# LAMEBOY.net
KiCad netlist of a schematic drawn in EAGLE
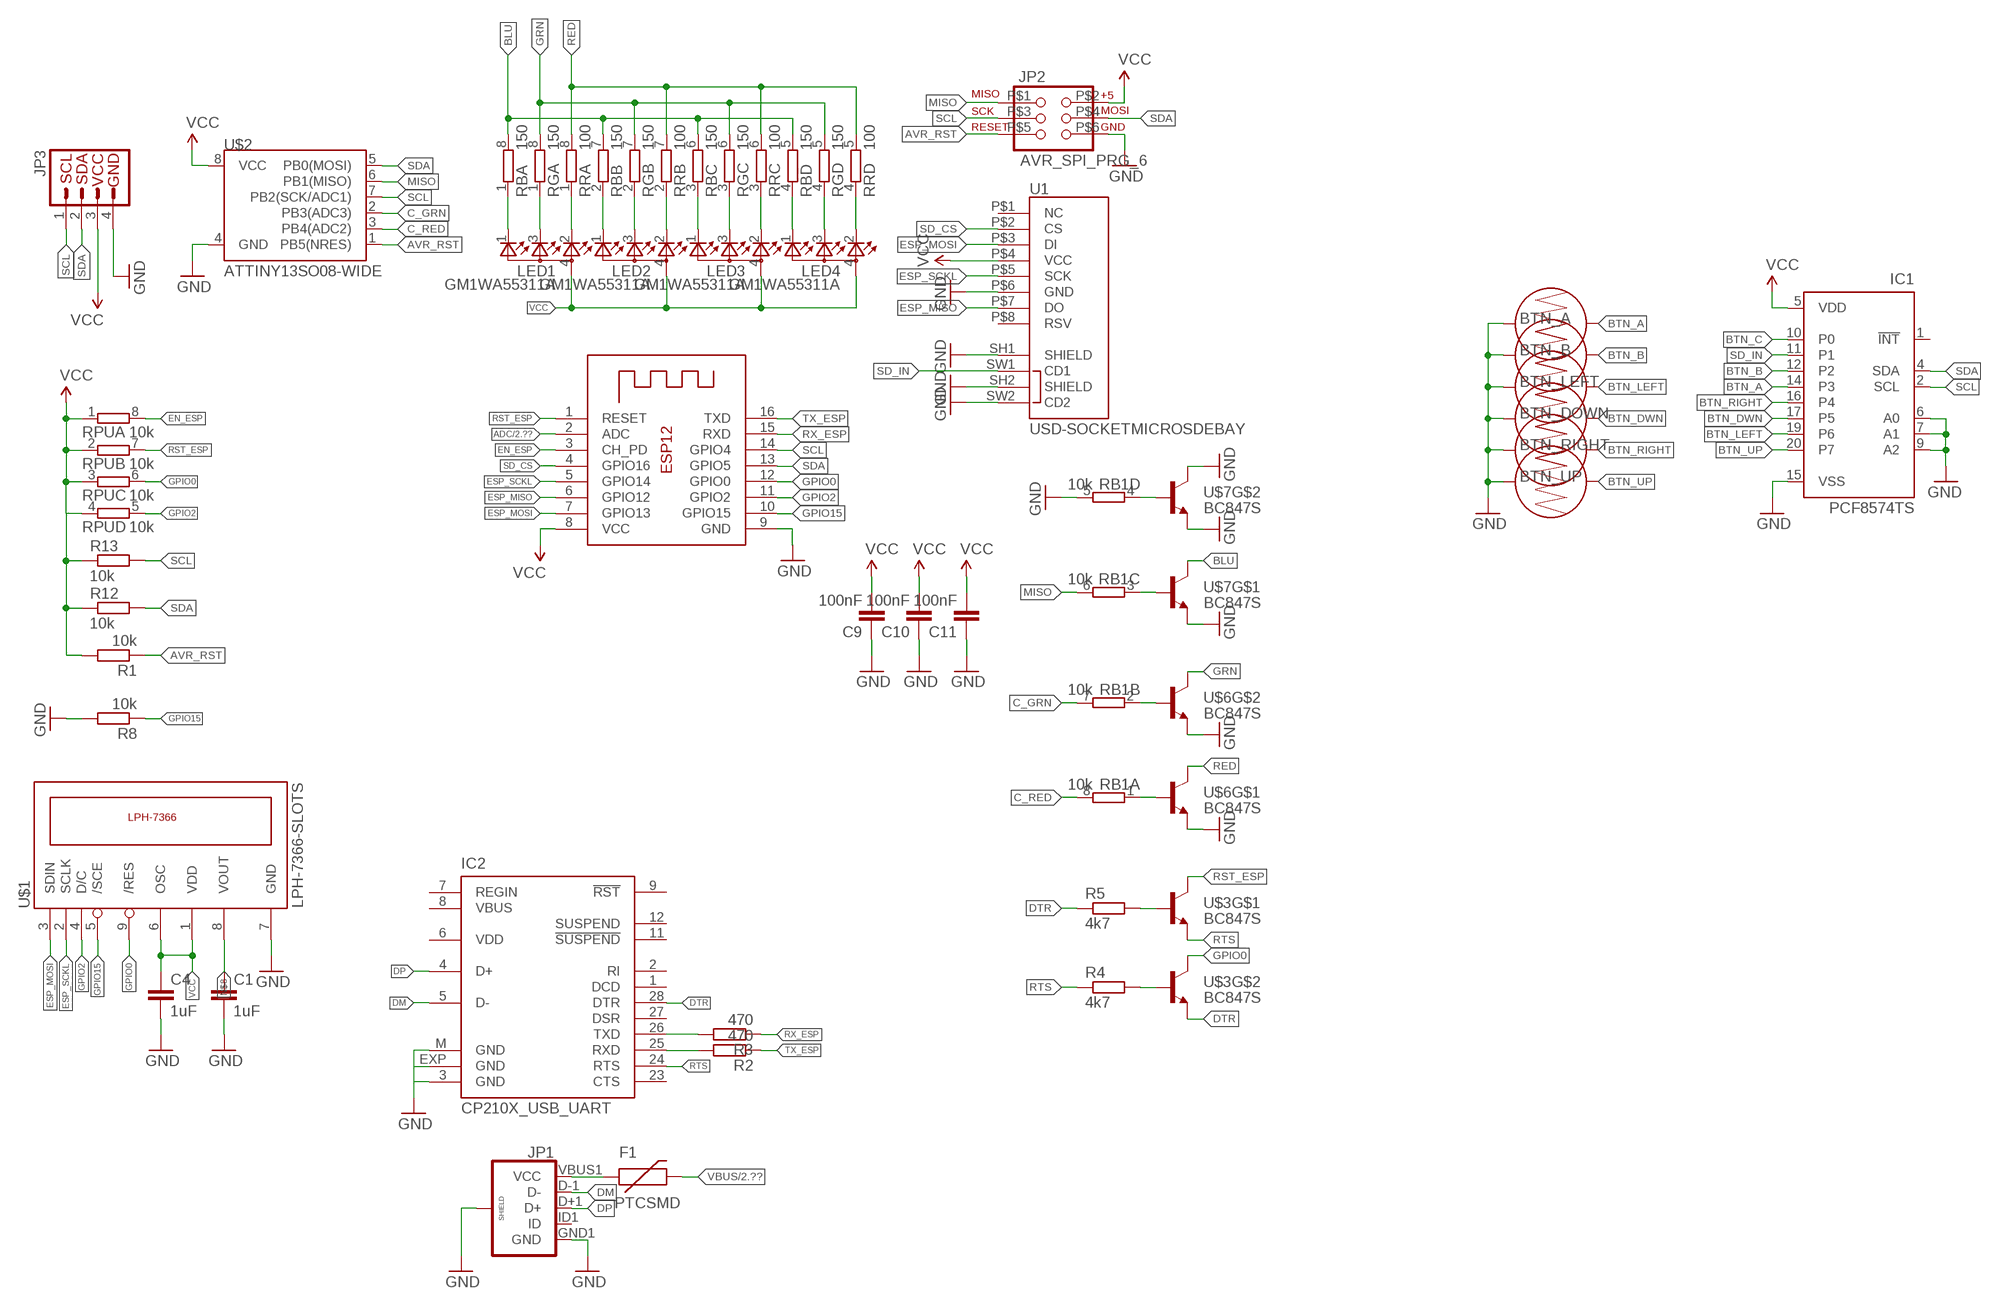
[diagram p0: schematic, sheet 1]
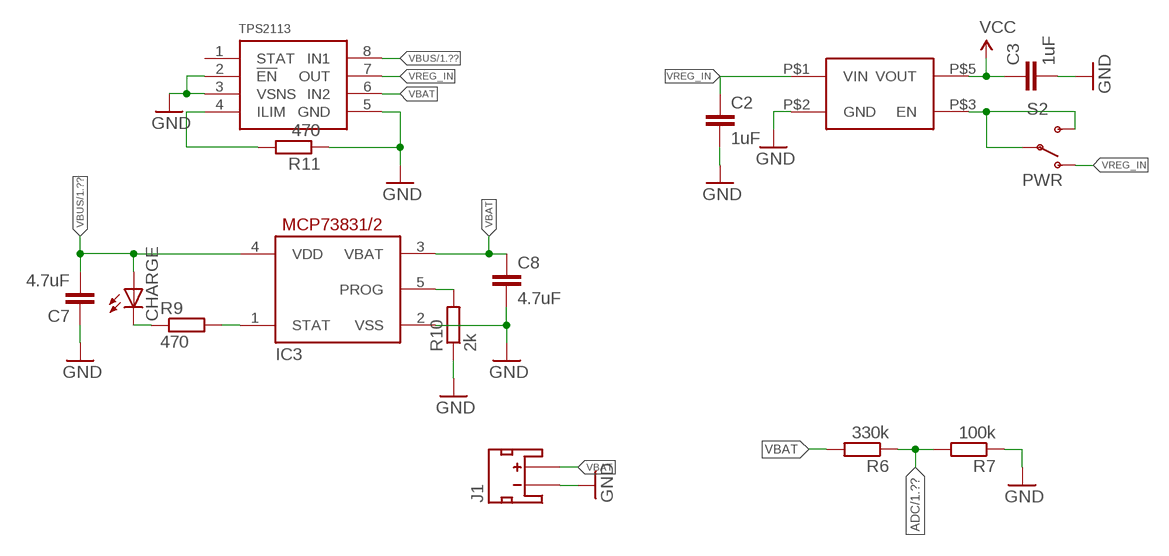
[diagram p1: schematic, sheet 2]

(export (version "E")
  (design (tool "Eeschema 10.0.6"))
  (components
    (comp (ref "C2")
      (value "1uF")
      (footprint "eagle-import:C0805")
      (libsource (lib "eagle-import") (part "C-EUC0805"))
    )
    (comp (ref "C3")
      (value "1uF")
      (footprint "eagle-import:C0805")
      (libsource (lib "eagle-import") (part "C-EUC0805"))
    )
    (comp (ref "C7")
      (value "4.7uF")
      (footprint "eagle-import:C0805")
      (libsource (lib "eagle-import") (part "C-EUC0805"))
    )
    (comp (ref "C8")
      (value "4.7uF")
      (footprint "eagle-import:C0805")
      (libsource (lib "eagle-import") (part "C-EUC0805"))
    )
    (comp (ref "CHARGE")
      (value "LEDCHARLIE")
      (footprint "eagle-import:CHIPLED_0603_CHARLIE")
      (libsource (lib "eagle-import") (part "LEDCHARLIE"))
    )
    (comp (ref "IC3")
      (value "MCP73831")
      (footprint "eagle-import:SOT23-5L")
      (libsource (lib "eagle-import") (part "MCP73831/OT"))
    )
    (comp (ref "J1")
      (value "JST_2MM_MALE")
      (footprint "eagle-import:JST-2-SMD")
      (libsource (lib "eagle-import") (part "JST_2MM_MALE"))
    )
    (comp (ref "R6")
      (value "330k")
      (footprint "eagle-import:R0805")
      (libsource (lib "eagle-import") (part "R-EU_R0805"))
    )
    (comp (ref "R7")
      (value "100k")
      (footprint "eagle-import:R0805")
      (libsource (lib "eagle-import") (part "R-EU_R0805"))
    )
    (comp (ref "R9")
      (value "470")
      (footprint "eagle-import:R0805")
      (libsource (lib "eagle-import") (part "R-EU_R0805"))
    )
    (comp (ref "R10")
      (value "2k")
      (footprint "eagle-import:R0805")
      (libsource (lib "eagle-import") (part "R-EU_R0805"))
    )
    (comp (ref "R11")
      (value "470")
      (footprint "eagle-import:M0805")
      (libsource (lib "eagle-import") (part "resistor_R-EU_M0805"))
    )
    (comp (ref "S2")
      (value "PWR")
      (footprint "eagle-import:SWITCH-SPST-SMD-A")
      (libsource (lib "eagle-import") (part "SWITCH-SPDT-SMD-A"))
    )
    (comp (ref "U$4")
      (value "TPS2113-PW")
      (footprint "eagle-import:TEXAS-PW")
      (libsource (lib "eagle-import") (part "TPS2113-PW"))
    )
    (comp (ref "U$9")
      (value "AP2112KAP2112K")
      (footprint "eagle-import:AP2112")
      (libsource (lib "eagle-import") (part "AP2112KAP2112K"))
    )
    (comp (ref "BTN_A")
      (value "BUTTON-CONDUCTIVESMD")
      (footprint "eagle-import:BUTTON-CONDUCTIVE")
      (libsource (lib "eagle-import") (part "BUTTON-CONDUCTIVESMD"))
    )
    (comp (ref "BTN_B")
      (value "BUTTON-CONDUCTIVESMD")
      (footprint "eagle-import:BUTTON-CONDUCTIVE")
      (libsource (lib "eagle-import") (part "BUTTON-CONDUCTIVESMD"))
    )
    (comp (ref "BTN_DOWN")
      (value "BUTTON-CONDUCTIVESMD")
      (footprint "eagle-import:BUTTON-CONDUCTIVE")
      (libsource (lib "eagle-import") (part "BUTTON-CONDUCTIVESMD"))
    )
    (comp (ref "BTN_LEFT")
      (value "BUTTON-CONDUCTIVESMD")
      (footprint "eagle-import:BUTTON-CONDUCTIVE")
      (libsource (lib "eagle-import") (part "BUTTON-CONDUCTIVESMD"))
    )
    (comp (ref "BTN_RIGHT")
      (value "BUTTON-CONDUCTIVESMD")
      (footprint "eagle-import:BUTTON-CONDUCTIVE")
      (libsource (lib "eagle-import") (part "BUTTON-CONDUCTIVESMD"))
    )
    (comp (ref "BTN_UP")
      (value "BUTTON-CONDUCTIVESMD")
      (footprint "eagle-import:BUTTON-CONDUCTIVE")
      (libsource (lib "eagle-import") (part "BUTTON-CONDUCTIVESMD"))
    )
    (comp (ref "C1")
      (value "1uF")
      (footprint "eagle-import:C0805")
      (libsource (lib "eagle-import") (part "C-EUC0805"))
    )
    (comp (ref "C4")
      (value "1uF")
      (footprint "eagle-import:C0805")
      (libsource (lib "eagle-import") (part "C-EUC0805"))
    )
    (comp (ref "C9")
      (value "100nF")
      (footprint "eagle-import:C0805")
      (libsource (lib "eagle-import") (part "C-EUC0805"))
    )
    (comp (ref "C10")
      (value "100nF")
      (footprint "eagle-import:C0805")
      (libsource (lib "eagle-import") (part "C-EUC0805"))
    )
    (comp (ref "C11")
      (value "100nF")
      (footprint "eagle-import:C0805")
      (libsource (lib "eagle-import") (part "C-EUC0805"))
    )
    (comp (ref "F1")
      (value "PTCSMD")
      (footprint "eagle-import:PTC-1206")
      (libsource (lib "eagle-import") (part "PTCSMD"))
    )
    (comp (ref "IC1")
      (value "PCF8574TS")
      (footprint "eagle-import:SSOP20")
      (fields (field (name "MPN") "PCF8574TS/3,118"))
      (libsource (lib "eagle-import") (part "PCF8574TS"))
    )
    (comp (ref "IC2")
      (value "CP210X_USB_UART")
      (footprint "eagle-import:MLP28")
      (libsource (lib "eagle-import") (part "CP210X_USB_UART"))
    )
    (comp (ref "JP1")
      (value "USB_MICROB_PLUG-IDK")
      (footprint "eagle-import:USB-AB-MICRO-SMD_SLOT")
      (libsource (lib "eagle-import") (part "USB_MICROB_PLUG-IDK"))
    )
    (comp (ref "JP2")
      (value "AVR_SPI_PRG_6")
      (footprint "eagle-import:2X3_SMD_PAD")
      (libsource (lib "eagle-import") (part "AVR_SPI_PRG_6"))
    )
    (comp (ref "JP3")
      (value "I2C_STANDARDI2C_JST")
      (footprint "eagle-import:S4B-PH")
      (libsource (lib "eagle-import") (part "I2C_STANDARDI2C_JST"))
    )
    (comp (ref "LED1")
      (value "GM1WA55311A")
      (footprint "eagle-import:GM1WA55311A")
      (libsource (lib "eagle-import") (part "GM1WA55311A"))
    )
    (comp (ref "LED2")
      (value "GM1WA55311A")
      (footprint "eagle-import:GM1WA55311A")
      (libsource (lib "eagle-import") (part "GM1WA55311A"))
    )
    (comp (ref "LED3")
      (value "GM1WA55311A")
      (footprint "eagle-import:GM1WA55311A")
      (libsource (lib "eagle-import") (part "GM1WA55311A"))
    )
    (comp (ref "LED4")
      (value "GM1WA55311A")
      (footprint "eagle-import:GM1WA55311A")
      (libsource (lib "eagle-import") (part "GM1WA55311A"))
    )
    (comp (ref "R1")
      (value "10k")
      (footprint "eagle-import:R0805")
      (libsource (lib "eagle-import") (part "R-EU_R0805"))
    )
    (comp (ref "R2")
      (value "470")
      (footprint "eagle-import:R0805")
      (libsource (lib "eagle-import") (part "R-EU_R0805"))
    )
    (comp (ref "R3")
      (value "470")
      (footprint "eagle-import:R0805")
      (libsource (lib "eagle-import") (part "R-EU_R0805"))
    )
    (comp (ref "R4")
      (value "4k7")
      (footprint "eagle-import:R0805")
      (libsource (lib "eagle-import") (part "R-EU_R0805"))
    )
    (comp (ref "R5")
      (value "4k7")
      (footprint "eagle-import:R0805")
      (libsource (lib "eagle-import") (part "R-EU_R0805"))
    )
    (comp (ref "R8")
      (value "10k")
      (footprint "eagle-import:R0805")
      (libsource (lib "eagle-import") (part "R-EU_R0805"))
    )
    (comp (ref "R12")
      (value "10k")
      (footprint "eagle-import:R0805")
      (libsource (lib "eagle-import") (part "R-EU_R0805"))
    )
    (comp (ref "R13")
      (value "10k")
      (footprint "eagle-import:R0805")
      (libsource (lib "eagle-import") (part "R-EU_R0805"))
    )
    (comp (ref "RB")
      (value "150")
      (footprint "eagle-import:0603-ARC")
      (libsource (lib "eagle-import") (part "4R-N0603-ARC"))
    )
    (comp (ref "RB1")
      (value "10k")
      (footprint "eagle-import:0603-ARC")
      (libsource (lib "eagle-import") (part "4R-N0603-ARC"))
    )
    (comp (ref "RG")
      (value "150")
      (footprint "eagle-import:0603-ARC")
      (libsource (lib "eagle-import") (part "4R-N0603-ARC"))
    )
    (comp (ref "RPU")
      (value "10k")
      (footprint "eagle-import:0603-ARC")
      (libsource (lib "eagle-import") (part "4R-N0603-ARC"))
    )
    (comp (ref "RR")
      (value "100")
      (footprint "eagle-import:0603-ARC")
      (libsource (lib "eagle-import") (part "4R-N0603-ARC"))
    )
    (comp (ref "U$1")
      (value "LPH-7366-SLOTS")
      (footprint "eagle-import:LPH-7366-SLOTS")
      (libsource (lib "eagle-import") (part "LPH-7366-SLOTS"))
    )
    (comp (ref "U$2")
      (value "ATTINY13SO08-WIDE")
      (footprint "eagle-import:SO08-EIAJ")
      (libsource (lib "eagle-import") (part "ATTINY13SO08-WIDE"))
    )
    (comp (ref "U$3")
      (value "BC847S")
      (footprint "eagle-import:SOT363")
      (libsource (lib "eagle-import") (part "MMDT3904"))
    )
    (comp (ref "U$6")
      (value "BC847S")
      (footprint "eagle-import:SOT363")
      (libsource (lib "eagle-import") (part "MMDT3904"))
    )
    (comp (ref "U$7")
      (value "BC847S")
      (footprint "eagle-import:SOT363")
      (libsource (lib "eagle-import") (part "MMDT3904"))
    )
    (comp (ref "U1")
      (value "USD-SOCKETMICROSDEBAY")
      (footprint "eagle-import:MICRO-SD-SOCKET-EBAY")
      (libsource (lib "eagle-import") (part "USD-SOCKETMICROSDEBAY"))
    )
    (comp (ref "X1")
      (value "ESP-12")
      (footprint "eagle-import:ESP-12")
      (libsource (lib "eagle-import") (part "ESP-12"))
    )
  )
  (nets
    (net (code "1") (name "ADC") (class "Default")
      (node (ref "R6") (pin "1") (pinfunction "1_1") (pintype "passive"))
      (node (ref "R7") (pin "2") (pinfunction "2_2") (pintype "passive"))
      (node (ref "X1") (pin "2") (pinfunction "ADC_2") (pintype "passive"))
    )
    (net (code "2") (name "AVR_RST") (class "Default")
      (node (ref "JP2") (pin "P$5") (pinfunction "5_P$5") (pintype "passive"))
      (node (ref "R1") (pin "1") (pinfunction "1_1") (pintype "passive"))
      (node (ref "U$2") (pin "1") (pinfunction "PB5(NRES)_1") (pintype "bidirectional"))
    )
    (net (code "3") (name "BLU") (class "Default")
      (node (ref "RB") (pin "5") (pinfunction "2_5") (pintype "passive"))
      (node (ref "RB") (pin "6") (pinfunction "2_6") (pintype "passive"))
      (node (ref "RB") (pin "7") (pinfunction "2_7") (pintype "passive"))
      (node (ref "RB") (pin "8") (pinfunction "2_8") (pintype "passive"))
      (node (ref "U$7") (pin "3") (pinfunction "C_3") (pintype "passive"))
    )
    (net (code "4") (name "BTN_A") (class "Default")
      (node (ref "BTN_A") (pin "2") (pinfunction "2_2") (pintype "passive"))
      (node (ref "IC1") (pin "14") (pinfunction "P3_14") (pintype "bidirectional"))
    )
    (net (code "5") (name "BTN_B") (class "Default")
      (node (ref "BTN_B") (pin "2") (pinfunction "2_2") (pintype "passive"))
      (node (ref "IC1") (pin "12") (pinfunction "P2_12") (pintype "bidirectional"))
    )
    (net (code "6") (name "BTN_C") (class "Default")
      (node (ref "IC1") (pin "10") (pinfunction "P0_10") (pintype "bidirectional"))
    )
    (net (code "7") (name "BTN_DWN") (class "Default")
      (node (ref "BTN_DOWN") (pin "2") (pinfunction "2_2") (pintype "passive"))
      (node (ref "IC1") (pin "17") (pinfunction "P5_17") (pintype "bidirectional"))
    )
    (net (code "8") (name "BTN_LEFT") (class "Default")
      (node (ref "BTN_LEFT") (pin "2") (pinfunction "2_2") (pintype "passive"))
      (node (ref "IC1") (pin "19") (pinfunction "P6_19") (pintype "bidirectional"))
    )
    (net (code "9") (name "BTN_RIGHT") (class "Default")
      (node (ref "BTN_RIGHT") (pin "2") (pinfunction "2_2") (pintype "passive"))
      (node (ref "IC1") (pin "16") (pinfunction "P4_16") (pintype "bidirectional"))
    )
    (net (code "10") (name "BTN_UP") (class "Default")
      (node (ref "BTN_UP") (pin "2") (pinfunction "2_2") (pintype "passive"))
      (node (ref "IC1") (pin "20") (pinfunction "P7_20") (pintype "bidirectional"))
    )
    (net (code "11") (name "C_GRN") (class "Default")
      (node (ref "RB1") (pin "7") (pinfunction "2_7") (pintype "passive"))
      (node (ref "U$2") (pin "2") (pinfunction "PB3(ADC3)_2") (pintype "bidirectional"))
    )
    (net (code "12") (name "C_RED") (class "Default")
      (node (ref "RB1") (pin "8") (pinfunction "2_8") (pintype "passive"))
      (node (ref "U$2") (pin "3") (pinfunction "PB4(ADC2)_3") (pintype "bidirectional"))
    )
    (net (code "13") (name "DM") (class "Default")
      (node (ref "IC2") (pin "5") (pinfunction "D-_5") (pintype "bidirectional"))
      (node (ref "JP1") (pin "D-1") (pinfunction "D-_D-1") (pintype "bidirectional"))
    )
    (net (code "14") (name "DP") (class "Default")
      (node (ref "IC2") (pin "4") (pinfunction "D+_4") (pintype "bidirectional"))
      (node (ref "JP1") (pin "D+1") (pinfunction "D+_D+1") (pintype "bidirectional"))
    )
    (net (code "15") (name "DTR") (class "Default")
      (node (ref "IC2") (pin "28") (pinfunction "DTR_28") (pintype "output"))
      (node (ref "R5") (pin "1") (pinfunction "1_1") (pintype "passive"))
      (node (ref "U$3") (pin "1") (pinfunction "E_1") (pintype "passive"))
    )
    (net (code "16") (name "EN_ESP") (class "Default")
      (node (ref "RPU") (pin "8") (pinfunction "2_8") (pintype "passive"))
      (node (ref "X1") (pin "3") (pinfunction "CH_PD_3") (pintype "input"))
    )
    (net (code "17") (name "ESP_MISO") (class "Default")
      (node (ref "U1") (pin "P$7") (pinfunction "DO_P$7") (pintype "bidirectional"))
      (node (ref "X1") (pin "6") (pinfunction "GPIO12_6") (pintype "bidirectional"))
    )
    (net (code "18") (name "ESP_MOSI") (class "Default")
      (node (ref "U$1") (pin "3") (pinfunction "SDIN_3") (pintype "input"))
      (node (ref "U1") (pin "P$3") (pinfunction "DI_P$3") (pintype "bidirectional"))
      (node (ref "X1") (pin "7") (pinfunction "GPIO13_7") (pintype "bidirectional"))
    )
    (net (code "19") (name "ESP_SCKL") (class "Default")
      (node (ref "U$1") (pin "2") (pinfunction "SCLK_2") (pintype "input"))
      (node (ref "U1") (pin "P$5") (pinfunction "SCK_P$5") (pintype "bidirectional"))
      (node (ref "X1") (pin "5") (pinfunction "GPIO14_5") (pintype "bidirectional"))
    )
    (net (code "20") (name "GND") (class "Default")
      (node (ref "BTN_A") (pin "1") (pinfunction "1_1") (pintype "passive"))
      (node (ref "BTN_B") (pin "1") (pinfunction "1_1") (pintype "passive"))
      (node (ref "BTN_DOWN") (pin "1") (pinfunction "1_1") (pintype "passive"))
      (node (ref "BTN_LEFT") (pin "1") (pinfunction "1_1") (pintype "passive"))
      (node (ref "BTN_RIGHT") (pin "1") (pinfunction "1_1") (pintype "passive"))
      (node (ref "BTN_UP") (pin "1") (pinfunction "1_1") (pintype "passive"))
      (node (ref "C1") (pin "2") (pinfunction "2_2") (pintype "passive"))
      (node (ref "C10") (pin "1") (pinfunction "1_1") (pintype "passive"))
      (node (ref "C11") (pin "1") (pinfunction "1_1") (pintype "passive"))
      (node (ref "C2") (pin "2") (pinfunction "2_2") (pintype "passive"))
      (node (ref "C3") (pin "2") (pinfunction "2_2") (pintype "passive"))
      (node (ref "C4") (pin "2") (pinfunction "2_2") (pintype "passive"))
      (node (ref "C7") (pin "1") (pinfunction "1_1") (pintype "passive"))
      (node (ref "C8") (pin "2") (pinfunction "2_2") (pintype "passive"))
      (node (ref "C9") (pin "1") (pinfunction "1_1") (pintype "passive"))
      (node (ref "IC1") (pin "15") (pinfunction "VSS_15") (pintype "power_in"))
      (node (ref "IC1") (pin "6") (pinfunction "A0_6") (pintype "input"))
      (node (ref "IC1") (pin "7") (pinfunction "A1_7") (pintype "input"))
      (node (ref "IC1") (pin "9") (pinfunction "A2_9") (pintype "input"))
      (node (ref "IC2") (pin "3") (pinfunction "GND_3") (pintype "power_in"))
      (node (ref "IC2") (pin "EXP") (pinfunction "GND_EXP") (pintype "power_in"))
      (node (ref "IC2") (pin "M") (pinfunction "GND_M") (pintype "power_in"))
      (node (ref "IC3") (pin "2") (pinfunction "VSS_2") (pintype "power_in"))
      (node (ref "J1") (pin "1") (pinfunction "-_1") (pintype "bidirectional"))
      (node (ref "JP1") (pin "GND1") (pinfunction "GND_GND1") (pintype "bidirectional"))
      (node (ref "JP1") (pin "P$1") (pinfunction "SHIELD_P$1") (pintype "bidirectional"))
      (node (ref "JP1") (pin "P$2") (pinfunction "SHIELD_P$2") (pintype "bidirectional"))
      (node (ref "JP1") (pin "P$3") (pinfunction "SHIELD_P$3") (pintype "bidirectional"))
      (node (ref "JP1") (pin "P$4") (pinfunction "SHIELD_P$4") (pintype "bidirectional"))
      (node (ref "JP2") (pin "P$6") (pinfunction "6_P$6") (pintype "passive"))
      (node (ref "JP3") (pin "4") (pinfunction "1_4") (pintype "passive"))
      (node (ref "R10") (pin "1") (pinfunction "1_1") (pintype "passive"))
      (node (ref "R11") (pin "1") (pinfunction "1_1") (pintype "passive"))
      (node (ref "R7") (pin "1") (pinfunction "1_1") (pintype "passive"))
      (node (ref "R8") (pin "2") (pinfunction "2_2") (pintype "passive"))
      (node (ref "RB1") (pin "5") (pinfunction "2_5") (pintype "passive"))
      (node (ref "U$1") (pin "7") (pinfunction "GND_7") (pintype "power_in"))
      (node (ref "U$2") (pin "4") (pinfunction "GND_4") (pintype "bidirectional"))
      (node (ref "U$4") (pin "2") (pinfunction "~{EN}_2") (pintype "bidirectional"))
      (node (ref "U$4") (pin "3") (pinfunction "VSNS_3") (pintype "bidirectional"))
      (node (ref "U$4") (pin "5") (pinfunction "GND_5") (pintype "bidirectional"))
      (node (ref "U$6") (pin "1") (pinfunction "E_1") (pintype "passive"))
      (node (ref "U$6") (pin "4") (pinfunction "E_4") (pintype "passive"))
      (node (ref "U$7") (pin "1") (pinfunction "E_1") (pintype "passive"))
      (node (ref "U$7") (pin "4") (pinfunction "E_4") (pintype "passive"))
      (node (ref "U$7") (pin "6") (pinfunction "C_6") (pintype "passive"))
      (node (ref "U$9") (pin "P$2") (pinfunction "GND_P$2") (pintype "bidirectional"))
      (node (ref "U1") (pin "P$6") (pinfunction "GND_P$6") (pintype "bidirectional"))
      (node (ref "U1") (pin "SH1") (pinfunction "SHIELD_SH1") (pintype "bidirectional"))
      (node (ref "U1") (pin "SH2") (pinfunction "SHIELD_SH2") (pintype "bidirectional"))
      (node (ref "U1") (pin "SW2") (pinfunction "CD2_SW2") (pintype "bidirectional"))
      (node (ref "X1") (pin "9") (pinfunction "GND_9") (pintype "power_in"))
    )
    (net (code "21") (name "GPIO0") (class "Default")
      (node (ref "RPU") (pin "6") (pinfunction "2_6") (pintype "passive"))
      (node (ref "U$1") (pin "9") (pinfunction "/RES_9") (pintype "input"))
      (node (ref "U$3") (pin "6") (pinfunction "C_6") (pintype "passive"))
      (node (ref "X1") (pin "12") (pinfunction "GPIO0_12") (pintype "bidirectional"))
    )
    (net (code "22") (name "GPIO2") (class "Default")
      (node (ref "RPU") (pin "5") (pinfunction "2_5") (pintype "passive"))
      (node (ref "U$1") (pin "4") (pinfunction "D/C_4") (pintype "input"))
      (node (ref "X1") (pin "11") (pinfunction "GPIO2_11") (pintype "bidirectional"))
    )
    (net (code "23") (name "GPIO15") (class "Default")
      (node (ref "R8") (pin "1") (pinfunction "1_1") (pintype "passive"))
      (node (ref "U$1") (pin "5") (pinfunction "/SCE_5") (pintype "input"))
      (node (ref "X1") (pin "10") (pinfunction "GPIO15_10") (pintype "bidirectional"))
    )
    (net (code "24") (name "GRN") (class "Default")
      (node (ref "RG") (pin "5") (pinfunction "2_5") (pintype "passive"))
      (node (ref "RG") (pin "6") (pinfunction "2_6") (pintype "passive"))
      (node (ref "RG") (pin "7") (pinfunction "2_7") (pintype "passive"))
      (node (ref "RG") (pin "8") (pinfunction "2_8") (pintype "passive"))
      (node (ref "U$6") (pin "6") (pinfunction "C_6") (pintype "passive"))
    )
    (net (code "25") (name "MISO") (class "Default")
      (node (ref "JP2") (pin "P$1") (pinfunction "1_P$1") (pintype "passive"))
      (node (ref "RB1") (pin "6") (pinfunction "2_6") (pintype "passive"))
      (node (ref "U$2") (pin "6") (pinfunction "PB1(MISO)_6") (pintype "bidirectional"))
    )
    (net (code "26") (name "N$8") (class "Default")
      (node (ref "C1") (pin "1") (pinfunction "1_1") (pintype "passive"))
      (node (ref "U$1") (pin "8") (pinfunction "VOUT_8") (pintype "passive"))
    )
    (net (code "27") (name "Net-(CHARGE-PadC)") (class "Default")
      (node (ref "CHARGE") (pin "C") (pinfunction "C_C") (pintype "passive"))
      (node (ref "R9") (pin "1") (pinfunction "1_1") (pintype "passive"))
    )
    (net (code "28") (name "Net-(IC2-RXD)") (class "Default")
      (node (ref "IC2") (pin "25") (pinfunction "RXD_25") (pintype "input"))
      (node (ref "R2") (pin "2") (pinfunction "2_2") (pintype "passive"))
    )
    (net (code "29") (name "Net-(IC2-TXD)") (class "Default")
      (node (ref "IC2") (pin "26") (pinfunction "TXD_26") (pintype "output"))
      (node (ref "R3") (pin "2") (pinfunction "2_2") (pintype "passive"))
    )
    (net (code "30") (name "Net-(IC3-PROG)") (class "Default")
      (node (ref "IC3") (pin "5") (pinfunction "PROG_5") (pintype "input"))
      (node (ref "R10") (pin "2") (pinfunction "2_2") (pintype "passive"))
    )
    (net (code "31") (name "Net-(IC3-STAT)") (class "Default")
      (node (ref "IC3") (pin "1") (pinfunction "STAT_1") (pintype "output"))
      (node (ref "R9") (pin "2") (pinfunction "2_2") (pintype "passive"))
    )
    (net (code "32") (name "Net-(JP1-VCC)") (class "Default")
      (node (ref "F1") (pin "1") (pinfunction "1_1") (pintype "bidirectional"))
      (node (ref "JP1") (pin "VBUS1") (pinfunction "VCC_VBUS1") (pintype "bidirectional"))
    )
    (net (code "33") (name "Net-(LED1-CBLUE)") (class "Default")
      (node (ref "LED1") (pin "3") (pinfunction "CBLUE_3") (pintype "passive"))
      (node (ref "RG") (pin "1") (pinfunction "1_1") (pintype "passive"))
    )
    (net (code "34") (name "Net-(LED1-CGREEN)") (class "Default")
      (node (ref "LED1") (pin "1") (pinfunction "CGREEN_1") (pintype "passive"))
      (node (ref "RB") (pin "1") (pinfunction "1_1") (pintype "passive"))
    )
    (net (code "35") (name "Net-(LED1-CRED)") (class "Default")
      (node (ref "LED1") (pin "2") (pinfunction "CRED_2") (pintype "passive"))
      (node (ref "RR") (pin "1") (pinfunction "1_1") (pintype "passive"))
    )
    (net (code "36") (name "Net-(LED2-CBLUE)") (class "Default")
      (node (ref "LED2") (pin "3") (pinfunction "CBLUE_3") (pintype "passive"))
      (node (ref "RG") (pin "2") (pinfunction "1_2") (pintype "passive"))
    )
    (net (code "37") (name "Net-(LED2-CGREEN)") (class "Default")
      (node (ref "LED2") (pin "1") (pinfunction "CGREEN_1") (pintype "passive"))
      (node (ref "RB") (pin "2") (pinfunction "1_2") (pintype "passive"))
    )
    (net (code "38") (name "Net-(LED2-CRED)") (class "Default")
      (node (ref "LED2") (pin "2") (pinfunction "CRED_2") (pintype "passive"))
      (node (ref "RR") (pin "2") (pinfunction "1_2") (pintype "passive"))
    )
    (net (code "39") (name "Net-(LED3-CBLUE)") (class "Default")
      (node (ref "LED3") (pin "3") (pinfunction "CBLUE_3") (pintype "passive"))
      (node (ref "RG") (pin "3") (pinfunction "1_3") (pintype "passive"))
    )
    (net (code "40") (name "Net-(LED3-CGREEN)") (class "Default")
      (node (ref "LED3") (pin "1") (pinfunction "CGREEN_1") (pintype "passive"))
      (node (ref "RB") (pin "3") (pinfunction "1_3") (pintype "passive"))
    )
    (net (code "41") (name "Net-(LED3-CRED)") (class "Default")
      (node (ref "LED3") (pin "2") (pinfunction "CRED_2") (pintype "passive"))
      (node (ref "RR") (pin "3") (pinfunction "1_3") (pintype "passive"))
    )
    (net (code "42") (name "Net-(LED4-CBLUE)") (class "Default")
      (node (ref "LED4") (pin "3") (pinfunction "CBLUE_3") (pintype "passive"))
      (node (ref "RG") (pin "4") (pinfunction "1_4") (pintype "passive"))
    )
    (net (code "43") (name "Net-(LED4-CGREEN)") (class "Default")
      (node (ref "LED4") (pin "1") (pinfunction "CGREEN_1") (pintype "passive"))
      (node (ref "RB") (pin "4") (pinfunction "1_4") (pintype "passive"))
    )
    (net (code "44") (name "Net-(LED4-CRED)") (class "Default")
      (node (ref "LED4") (pin "2") (pinfunction "CRED_2") (pintype "passive"))
      (node (ref "RR") (pin "4") (pinfunction "1_4") (pintype "passive"))
    )
    (net (code "45") (name "Net-(RB1B-1)") (class "Default")
      (node (ref "RB1") (pin "2") (pinfunction "1_2") (pintype "passive"))
      (node (ref "U$6") (pin "2") (pinfunction "B_2") (pintype "passive"))
    )
    (net (code "46") (name "Net-(RB1C-1)") (class "Default")
      (node (ref "RB1") (pin "3") (pinfunction "1_3") (pintype "passive"))
      (node (ref "U$7") (pin "5") (pinfunction "B_5") (pintype "passive"))
    )
    (net (code "47") (name "Net-(RB1D-1)") (class "Default")
      (node (ref "RB1") (pin "4") (pinfunction "1_4") (pintype "passive"))
      (node (ref "U$7") (pin "2") (pinfunction "B_2") (pintype "passive"))
    )
    (net (code "48") (name "Net-(S2-P)") (class "Default")
      (node (ref "S2") (pin "2") (pinfunction "P_2") (pintype "passive"))
      (node (ref "S2") (pin "3") (pinfunction "S_3") (pintype "passive"))
      (node (ref "U$9") (pin "P$3") (pinfunction "EN_P$3") (pintype "bidirectional"))
    )
    (net (code "49") (name "Net-(U$3A-B)") (class "Default")
      (node (ref "R5") (pin "2") (pinfunction "2_2") (pintype "passive"))
      (node (ref "U$3") (pin "5") (pinfunction "B_5") (pintype "passive"))
    )
    (net (code "50") (name "Net-(U$3B-B)") (class "Default")
      (node (ref "R4") (pin "2") (pinfunction "2_2") (pintype "passive"))
      (node (ref "U$3") (pin "2") (pinfunction "B_2") (pintype "passive"))
    )
    (net (code "51") (name "Net-(U$4-ILIM)") (class "Default")
      (node (ref "R11") (pin "2") (pinfunction "2_2") (pintype "passive"))
      (node (ref "U$4") (pin "4") (pinfunction "ILIM_4") (pintype "bidirectional"))
    )
    (net (code "52") (name "Net-(U$6A-B)") (class "Default")
      (node (ref "RB1") (pin "1") (pinfunction "1_1") (pintype "passive"))
      (node (ref "U$6") (pin "5") (pinfunction "B_5") (pintype "passive"))
    )
    (net (code "53") (name "RED") (class "Default")
      (node (ref "RR") (pin "5") (pinfunction "2_5") (pintype "passive"))
      (node (ref "RR") (pin "6") (pinfunction "2_6") (pintype "passive"))
      (node (ref "RR") (pin "7") (pinfunction "2_7") (pintype "passive"))
      (node (ref "RR") (pin "8") (pinfunction "2_8") (pintype "passive"))
      (node (ref "U$6") (pin "3") (pinfunction "C_3") (pintype "passive"))
    )
    (net (code "54") (name "RST_ESP") (class "Default")
      (node (ref "RPU") (pin "7") (pinfunction "2_7") (pintype "passive"))
      (node (ref "U$3") (pin "3") (pinfunction "C_3") (pintype "passive"))
      (node (ref "X1") (pin "1") (pinfunction "RESET_1") (pintype "input"))
    )
    (net (code "55") (name "RTS") (class "Default")
      (node (ref "IC2") (pin "24") (pinfunction "RTS_24") (pintype "output"))
      (node (ref "R4") (pin "1") (pinfunction "1_1") (pintype "passive"))
      (node (ref "U$3") (pin "4") (pinfunction "E_4") (pintype "passive"))
    )
    (net (code "56") (name "RX_ESP") (class "Default")
      (node (ref "R3") (pin "1") (pinfunction "1_1") (pintype "passive"))
      (node (ref "X1") (pin "15") (pinfunction "RXD_15") (pintype "input"))
    )
    (net (code "57") (name "SCL") (class "Default")
      (node (ref "IC1") (pin "2") (pinfunction "SCL_2") (pintype "input"))
      (node (ref "JP2") (pin "P$3") (pinfunction "3_P$3") (pintype "passive"))
      (node (ref "JP3") (pin "1") (pinfunction "4_1") (pintype "passive"))
      (node (ref "R13") (pin "2") (pinfunction "2_2") (pintype "passive"))
      (node (ref "U$2") (pin "7") (pinfunction "PB2(SCK/ADC1)_7") (pintype "bidirectional"))
      (node (ref "X1") (pin "14") (pinfunction "GPIO4_14") (pintype "bidirectional"))
    )
    (net (code "58") (name "SDA") (class "Default")
      (node (ref "IC1") (pin "4") (pinfunction "SDA_4") (pintype "bidirectional"))
      (node (ref "JP2") (pin "P$4") (pinfunction "4_P$4") (pintype "passive"))
      (node (ref "JP3") (pin "2") (pinfunction "3_2") (pintype "passive"))
      (node (ref "R12") (pin "2") (pinfunction "2_2") (pintype "passive"))
      (node (ref "U$2") (pin "5") (pinfunction "PB0(MOSI)_5") (pintype "bidirectional"))
      (node (ref "X1") (pin "13") (pinfunction "GPIO5_13") (pintype "bidirectional"))
    )
    (net (code "59") (name "SD_CS") (class "Default")
      (node (ref "U1") (pin "P$2") (pinfunction "CS_P$2") (pintype "bidirectional"))
      (node (ref "X1") (pin "4") (pinfunction "GPIO16_4") (pintype "bidirectional"))
    )
    (net (code "60") (name "SD_IN") (class "Default")
      (node (ref "IC1") (pin "11") (pinfunction "P1_11") (pintype "bidirectional"))
      (node (ref "U1") (pin "SW1") (pinfunction "CD1_SW1") (pintype "bidirectional"))
    )
    (net (code "61") (name "TX_ESP") (class "Default")
      (node (ref "R2") (pin "1") (pinfunction "1_1") (pintype "passive"))
      (node (ref "X1") (pin "16") (pinfunction "TXD_16") (pintype "output"))
    )
    (net (code "62") (name "VBAT") (class "Default")
      (node (ref "C8") (pin "1") (pinfunction "1_1") (pintype "passive"))
      (node (ref "IC3") (pin "3") (pinfunction "VBAT_3") (pintype "bidirectional"))
      (node (ref "J1") (pin "2") (pinfunction "+_2") (pintype "bidirectional"))
      (node (ref "R6") (pin "2") (pinfunction "2_2") (pintype "passive"))
      (node (ref "U$4") (pin "6") (pinfunction "IN2_6") (pintype "bidirectional"))
    )
    (net (code "63") (name "VBUS") (class "Default")
      (node (ref "C7") (pin "2") (pinfunction "2_2") (pintype "passive"))
      (node (ref "CHARGE") (pin "A") (pinfunction "A_A") (pintype "passive"))
      (node (ref "F1") (pin "2") (pinfunction "2_2") (pintype "bidirectional"))
      (node (ref "IC3") (pin "4") (pinfunction "VDD_4") (pintype "power_in"))
      (node (ref "U$4") (pin "8") (pinfunction "IN1_8") (pintype "bidirectional"))
    )
    (net (code "64") (name "VCC") (class "Default")
      (node (ref "C10") (pin "2") (pinfunction "2_2") (pintype "passive"))
      (node (ref "C11") (pin "2") (pinfunction "2_2") (pintype "passive"))
      (node (ref "C3") (pin "1") (pinfunction "1_1") (pintype "passive"))
      (node (ref "C4") (pin "1") (pinfunction "1_1") (pintype "passive"))
      (node (ref "C9") (pin "2") (pinfunction "2_2") (pintype "passive"))
      (node (ref "IC1") (pin "5") (pinfunction "VDD_5") (pintype "power_in"))
      (node (ref "JP2") (pin "P$2") (pinfunction "2_P$2") (pintype "passive"))
      (node (ref "JP3") (pin "3") (pinfunction "2_3") (pintype "passive"))
      (node (ref "LED1") (pin "4") (pinfunction "A_4") (pintype "passive"))
      (node (ref "LED2") (pin "4") (pinfunction "A_4") (pintype "passive"))
      (node (ref "LED3") (pin "4") (pinfunction "A_4") (pintype "passive"))
      (node (ref "LED4") (pin "4") (pinfunction "A_4") (pintype "passive"))
      (node (ref "R1") (pin "2") (pinfunction "2_2") (pintype "passive"))
      (node (ref "R12") (pin "1") (pinfunction "1_1") (pintype "passive"))
      (node (ref "R13") (pin "1") (pinfunction "1_1") (pintype "passive"))
      (node (ref "RPU") (pin "1") (pinfunction "1_1") (pintype "passive"))
      (node (ref "RPU") (pin "2") (pinfunction "1_2") (pintype "passive"))
      (node (ref "RPU") (pin "3") (pinfunction "1_3") (pintype "passive"))
      (node (ref "RPU") (pin "4") (pinfunction "1_4") (pintype "passive"))
      (node (ref "U$1") (pin "1") (pinfunction "VDD_1") (pintype "power_in"))
      (node (ref "U$1") (pin "6") (pinfunction "OSC_6") (pintype "passive"))
      (node (ref "U$2") (pin "8") (pinfunction "VCC_8") (pintype "bidirectional"))
      (node (ref "U$9") (pin "P$5") (pinfunction "VOUT_P$5") (pintype "bidirectional"))
      (node (ref "U1") (pin "P$4") (pinfunction "VCC_P$4") (pintype "bidirectional"))
      (node (ref "X1") (pin "8") (pinfunction "VCC_8") (pintype "power_in"))
    )
    (net (code "65") (name "VDD") (class "Default")
      (node (ref "IC2") (pin "6") (pinfunction "VDD_6") (pintype "power_in"))
    )
    (net (code "66") (name "VREG_IN") (class "Default")
      (node (ref "C2") (pin "1") (pinfunction "1_1") (pintype "passive"))
      (node (ref "S2") (pin "1") (pinfunction "O_1") (pintype "passive"))
      (node (ref "U$4") (pin "7") (pinfunction "OUT_7") (pintype "bidirectional"))
      (node (ref "U$9") (pin "P$1") (pinfunction "VIN_P$1") (pintype "bidirectional"))
    )
    (net (code "67") (name "unconnected-(IC1-~{INT}-Pad1)") (class "Default")
      (node (ref "IC1") (pin "1") (pinfunction "~{INT}_1") (pintype "output"))
    )
    (net (code "68") (name "unconnected-(IC2-CTS-Pad23)") (class "Default")
      (node (ref "IC2") (pin "23") (pinfunction "CTS_23") (pintype "input"))
    )
    (net (code "69") (name "unconnected-(IC2-DCD-Pad1)") (class "Default")
      (node (ref "IC2") (pin "1") (pinfunction "DCD_1") (pintype "input"))
    )
    (net (code "70") (name "unconnected-(IC2-DSR-Pad27)") (class "Default")
      (node (ref "IC2") (pin "27") (pinfunction "DSR_27") (pintype "input"))
    )
    (net (code "71") (name "unconnected-(IC2-REGIN-Pad7)") (class "Default")
      (node (ref "IC2") (pin "7") (pinfunction "REGIN_7") (pintype "passive"))
    )
    (net (code "72") (name "unconnected-(IC2-RI-Pad2)") (class "Default")
      (node (ref "IC2") (pin "2") (pinfunction "RI_2") (pintype "input"))
    )
    (net (code "73") (name "unconnected-(IC2-SUSPEND-Pad12)") (class "Default")
      (node (ref "IC2") (pin "12") (pinfunction "SUSPEND_12") (pintype "output"))
    )
    (net (code "74") (name "unconnected-(IC2-VBUS-Pad8)") (class "Default")
      (node (ref "IC2") (pin "8") (pinfunction "VBUS_8") (pintype "input"))
    )
    (net (code "75") (name "unconnected-(IC2-~{RST}-Pad9)") (class "Default")
      (node (ref "IC2") (pin "9") (pinfunction "~{RST}_9") (pintype "bidirectional"))
    )
    (net (code "76") (name "unconnected-(IC2-~{SUSPEND}-Pad11)") (class "Default")
      (node (ref "IC2") (pin "11") (pinfunction "~{SUSPEND}_11") (pintype "output"))
    )
    (net (code "77") (name "unconnected-(J1-PAD1-PadNC1)") (class "Default")
      (node (ref "J1") (pin "NC1") (pinfunction "PAD1_NC1") (pintype "bidirectional"))
    )
    (net (code "78") (name "unconnected-(J1-PAD2-PadNC2)") (class "Default")
      (node (ref "J1") (pin "NC2") (pinfunction "PAD2_NC2") (pintype "bidirectional"))
    )
    (net (code "79") (name "unconnected-(JP1-ID-PadID1)") (class "Default")
      (node (ref "JP1") (pin "ID1") (pinfunction "ID_ID1") (pintype "bidirectional"))
    )
    (net (code "80") (name "unconnected-(U$4-STAT-Pad1)") (class "Default")
      (node (ref "U$4") (pin "1") (pinfunction "STAT_1") (pintype "bidirectional"))
    )
    (net (code "81") (name "unconnected-(U1-NC-PadP$1)") (class "Default")
      (node (ref "U1") (pin "P$1") (pinfunction "NC_P$1") (pintype "bidirectional"))
    )
    (net (code "82") (name "unconnected-(U1-RSV-PadP$8)") (class "Default")
      (node (ref "U1") (pin "P$8") (pinfunction "RSV_P$8") (pintype "bidirectional"))
    )
  )
)
